# Firmware_Update_Board.net
KiCad netlist of a schematic drawn in EAGLE
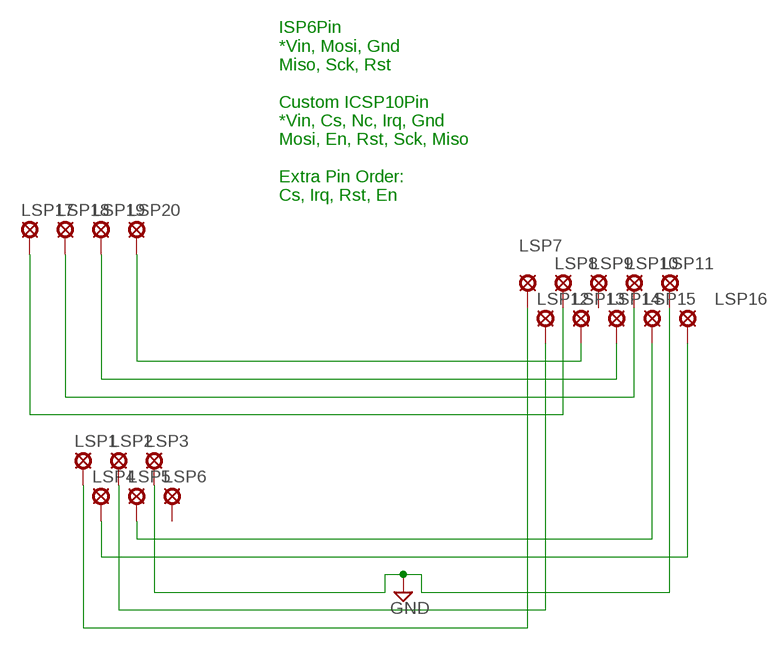
[diagram p0: schematic, sheet 1]

(export (version "E")
  (design (tool "Eeschema 10.0.6"))
  (components
    (comp (ref "LSP1")
      (value "LSP10_CLSP10_C")
      (footprint "eagle-import:LSP10_C")
      (libsource (lib "eagle-import") (part "LSP10_CLSP10_C"))
    )
    (comp (ref "LSP2")
      (value "LSP10_CLSP10_C")
      (footprint "eagle-import:LSP10_C")
      (libsource (lib "eagle-import") (part "LSP10_CLSP10_C"))
    )
    (comp (ref "LSP3")
      (value "LSP10_CLSP10_C")
      (footprint "eagle-import:LSP10_C")
      (libsource (lib "eagle-import") (part "LSP10_CLSP10_C"))
    )
    (comp (ref "LSP4")
      (value "LSP10_CLSP10_C")
      (footprint "eagle-import:LSP10_C")
      (libsource (lib "eagle-import") (part "LSP10_CLSP10_C"))
    )
    (comp (ref "LSP5")
      (value "LSP10_CLSP10_C")
      (footprint "eagle-import:LSP10_C")
      (libsource (lib "eagle-import") (part "LSP10_CLSP10_C"))
    )
    (comp (ref "LSP6")
      (value "LSP10_CLSP10_C")
      (footprint "eagle-import:LSP10_C")
      (libsource (lib "eagle-import") (part "LSP10_CLSP10_C"))
    )
    (comp (ref "LSP7")
      (value "LSP10_CLSP10_C")
      (footprint "eagle-import:LSP10_C")
      (libsource (lib "eagle-import") (part "LSP10_CLSP10_C"))
    )
    (comp (ref "LSP8")
      (value "LSP10_CLSP10_C")
      (footprint "eagle-import:LSP10_C")
      (libsource (lib "eagle-import") (part "LSP10_CLSP10_C"))
    )
    (comp (ref "LSP9")
      (value "LSP10_CLSP10_C")
      (footprint "eagle-import:LSP10_C")
      (libsource (lib "eagle-import") (part "LSP10_CLSP10_C"))
    )
    (comp (ref "LSP10")
      (value "LSP10_CLSP10_C")
      (footprint "eagle-import:LSP10_C")
      (libsource (lib "eagle-import") (part "LSP10_CLSP10_C"))
    )
    (comp (ref "LSP11")
      (value "LSP10_CLSP10_C")
      (footprint "eagle-import:LSP10_C")
      (libsource (lib "eagle-import") (part "LSP10_CLSP10_C"))
    )
    (comp (ref "LSP12")
      (value "LSP10_CLSP10_C")
      (footprint "eagle-import:LSP10_C")
      (libsource (lib "eagle-import") (part "LSP10_CLSP10_C"))
    )
    (comp (ref "LSP13")
      (value "LSP10_CLSP10_C")
      (footprint "eagle-import:LSP10_C")
      (libsource (lib "eagle-import") (part "LSP10_CLSP10_C"))
    )
    (comp (ref "LSP14")
      (value "LSP10_CLSP10_C")
      (footprint "eagle-import:LSP10_C")
      (libsource (lib "eagle-import") (part "LSP10_CLSP10_C"))
    )
    (comp (ref "LSP15")
      (value "LSP10_CLSP10_C")
      (footprint "eagle-import:LSP10_C")
      (libsource (lib "eagle-import") (part "LSP10_CLSP10_C"))
    )
    (comp (ref "LSP16")
      (value "LSP10_CLSP10_C")
      (footprint "eagle-import:LSP10_C")
      (libsource (lib "eagle-import") (part "LSP10_CLSP10_C"))
    )
    (comp (ref "LSP17")
      (value "LSP10_CLSP10_C")
      (footprint "eagle-import:LSP10_C")
      (libsource (lib "eagle-import") (part "LSP10_CLSP10_C"))
    )
    (comp (ref "LSP18")
      (value "LSP10_CLSP10_C")
      (footprint "eagle-import:LSP10_C")
      (libsource (lib "eagle-import") (part "LSP10_CLSP10_C"))
    )
    (comp (ref "LSP19")
      (value "LSP10_CLSP10_C")
      (footprint "eagle-import:LSP10_C")
      (libsource (lib "eagle-import") (part "LSP10_CLSP10_C"))
    )
    (comp (ref "LSP20")
      (value "LSP10_CLSP10_C")
      (footprint "eagle-import:LSP10_C")
      (libsource (lib "eagle-import") (part "LSP10_CLSP10_C"))
    )
  )
  (nets
    (net (code "1") (name "GND") (class "Default")
      (node (ref "LSP11") (pin "P$1") (pinfunction "MP_P$1") (pintype "passive"))
      (node (ref "LSP3") (pin "P$1") (pinfunction "MP_P$1") (pintype "passive"))
    )
    (net (code "2") (name "Net-(LSP1-MP)") (class "Default")
      (node (ref "LSP1") (pin "P$1") (pinfunction "MP_P$1") (pintype "passive"))
      (node (ref "LSP7") (pin "P$1") (pinfunction "MP_P$1") (pintype "passive"))
    )
    (net (code "3") (name "Net-(LSP10-MP)") (class "Default")
      (node (ref "LSP10") (pin "P$1") (pinfunction "MP_P$1") (pintype "passive"))
      (node (ref "LSP18") (pin "P$1") (pinfunction "MP_P$1") (pintype "passive"))
    )
    (net (code "4") (name "Net-(LSP12-MP)") (class "Default")
      (node (ref "LSP12") (pin "P$1") (pinfunction "MP_P$1") (pintype "passive"))
      (node (ref "LSP2") (pin "P$1") (pinfunction "MP_P$1") (pintype "passive"))
    )
    (net (code "5") (name "Net-(LSP13-MP)") (class "Default")
      (node (ref "LSP13") (pin "P$1") (pinfunction "MP_P$1") (pintype "passive"))
      (node (ref "LSP20") (pin "P$1") (pinfunction "MP_P$1") (pintype "passive"))
    )
    (net (code "6") (name "Net-(LSP14-MP)") (class "Default")
      (node (ref "LSP14") (pin "P$1") (pinfunction "MP_P$1") (pintype "passive"))
      (node (ref "LSP19") (pin "P$1") (pinfunction "MP_P$1") (pintype "passive"))
    )
    (net (code "7") (name "Net-(LSP15-MP)") (class "Default")
      (node (ref "LSP15") (pin "P$1") (pinfunction "MP_P$1") (pintype "passive"))
      (node (ref "LSP5") (pin "P$1") (pinfunction "MP_P$1") (pintype "passive"))
    )
    (net (code "8") (name "Net-(LSP16-MP)") (class "Default")
      (node (ref "LSP16") (pin "P$1") (pinfunction "MP_P$1") (pintype "passive"))
      (node (ref "LSP4") (pin "P$1") (pinfunction "MP_P$1") (pintype "passive"))
    )
    (net (code "9") (name "Net-(LSP17-MP)") (class "Default")
      (node (ref "LSP17") (pin "P$1") (pinfunction "MP_P$1") (pintype "passive"))
      (node (ref "LSP8") (pin "P$1") (pinfunction "MP_P$1") (pintype "passive"))
    )
    (net (code "10") (name "unconnected-(LSP6-MP-PadP$1)") (class "Default")
      (node (ref "LSP6") (pin "P$1") (pinfunction "MP_P$1") (pintype "passive"))
    )
    (net (code "11") (name "unconnected-(LSP9-MP-PadP$1)") (class "Default")
      (node (ref "LSP9") (pin "P$1") (pinfunction "MP_P$1") (pintype "passive"))
    )
  )
)
